# PhaseALeg.net
KiCad netlist of a schematic drawn in Altium Designer
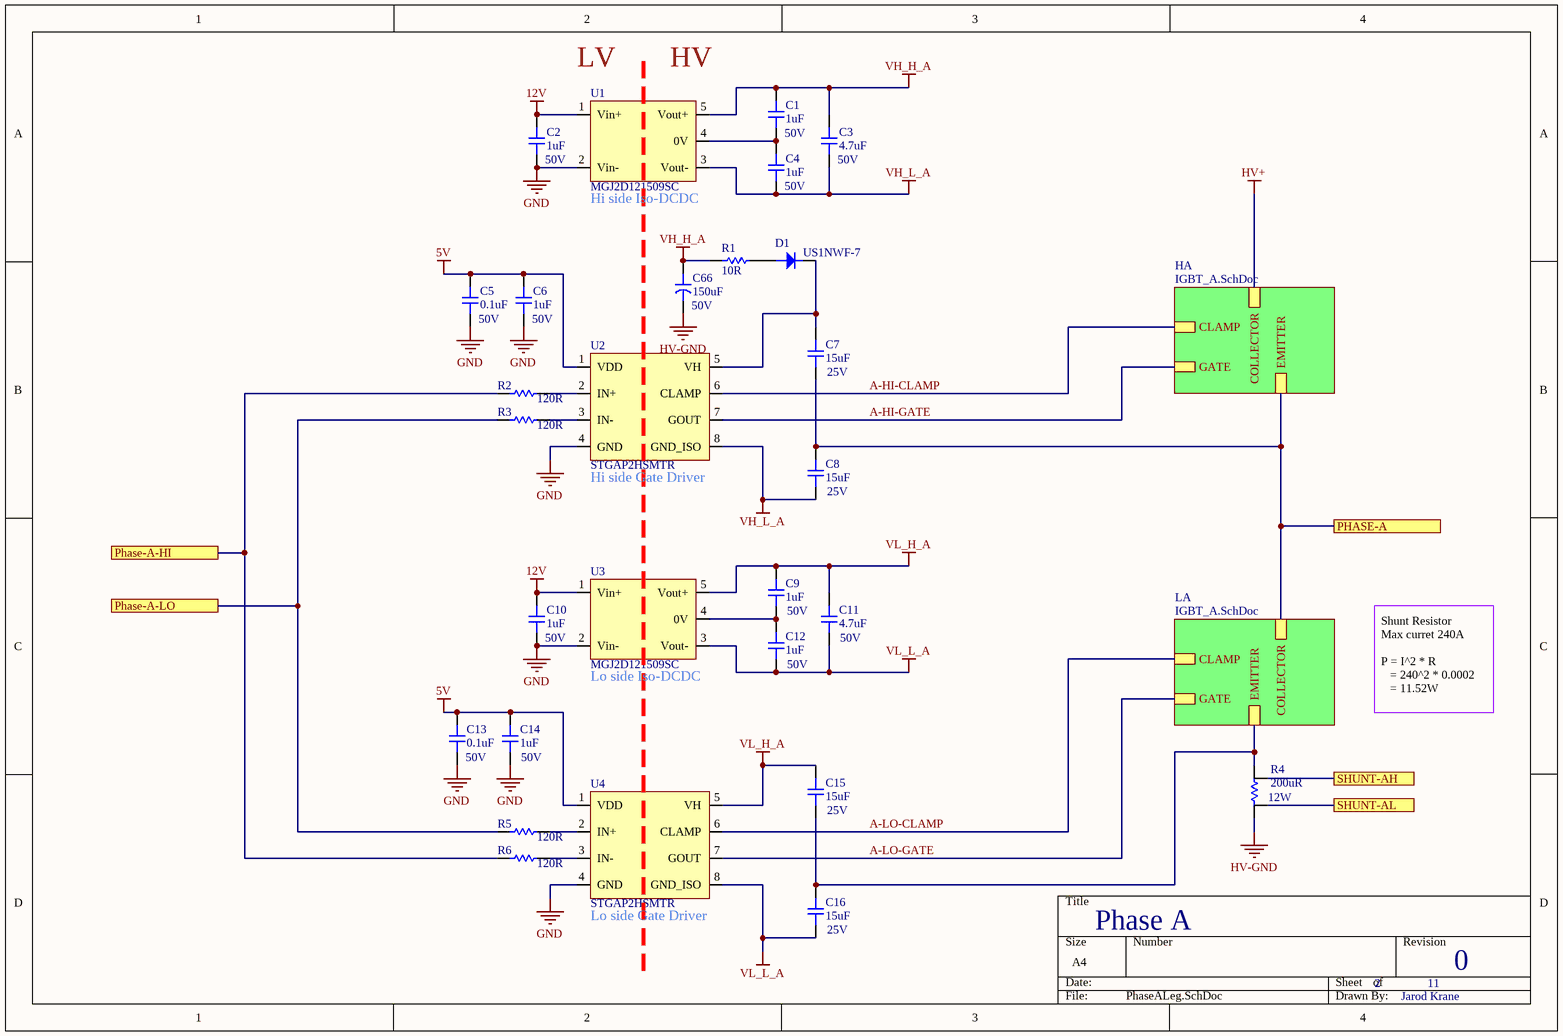
[diagram p0: PhaseALeg.SchDoc]

(export (version "E")
  (design (tool "Eeschema 10.0.6"))
  (components
    (comp (ref "C1")
      (value "1uF")
      (footprint "CAP-0805")
      (description "CAP CER 1UF 50V X5R 0805")
      (fields
        (field (name "MANUFACTURER") "KEMET")
        (field (name "MANUFACTURER PART NUMBER") "C0805C105K5PACTU")
        (field (name "VOLTAGE RATING") "50V")
      )
      (libsource (lib "InverterSCHLib") (part "0805-1uF-50V"))
    )
    (comp (ref "C2")
      (value "1uF")
      (footprint "CAP-0805")
      (description "CAP CER 1UF 50V X5R 0805")
      (fields
        (field (name "MANUFACTURER") "KEMET")
        (field (name "MANUFACTURER PART NUMBER") "C0805C105K5PACTU")
        (field (name "VOLTAGE RATING") "50V")
      )
      (libsource (lib "InverterSCHLib") (part "0805-1uF-50V"))
    )
    (comp (ref "C3")
      (value "4.7uF")
      (footprint "CAP-1206")
      (description "CAP CER 4.7UF 50V X7R 1206")
      (fields
        (field (name "MANUFACTURER") "TDK")
        (field (name "MANUFACTURER PART NUMBER") "C3216X7R1H475K160AC")
        (field (name "VOLTAGE RATING") "50V")
      )
      (libsource (lib "InverterSCHLib") (part "1206-4.7uF-50V"))
    )
    (comp (ref "C4")
      (value "1uF")
      (footprint "CAP-0805")
      (description "CAP CER 1UF 50V X5R 0805")
      (fields
        (field (name "MANUFACTURER") "KEMET")
        (field (name "MANUFACTURER PART NUMBER") "C0805C105K5PACTU")
        (field (name "VOLTAGE RATING") "50V")
      )
      (libsource (lib "InverterSCHLib") (part "0805-1uF-50V"))
    )
    (comp (ref "C5")
      (value "0.1uF")
      (footprint "CAP-0805")
      (description "CAP CER 0.1UF 50V Y5V 0805")
      (fields
        (field (name "MANUFACTURER") "KEMET")
        (field (name "MANUFACTURER PART NUMBER") "C0805C104Z5VACTU")
        (field (name "VOLTAGE") "50V")
      )
      (libsource (lib "InverterSCHLib") (part "0805-0.1uF-50V"))
    )
    (comp (ref "C6")
      (value "1uF")
      (footprint "CAP-0805")
      (description "CAP CER 1UF 50V X5R 0805")
      (fields
        (field (name "MANUFACTURER") "KEMET")
        (field (name "MANUFACTURER PART NUMBER") "C0805C105K5PACTU")
        (field (name "VOLTAGE RATING") "50V")
      )
      (libsource (lib "InverterSCHLib") (part "0805-1uF-50V"))
    )
    (comp (ref "C7")
      (value "15uF")
      (footprint "CAP-1812")
      (description "CAP CER 15UF 25V X7R 1812")
      (fields
        (field (name "MANUFACTURER") "TDK")
        (field (name "MANUFACTURER PART NUMBER") "C4532X7R1E156M280KB")
        (field (name "VOLTAGE") "25V")
      )
      (libsource (lib "InverterSCHLib") (part "1812-15uF-25V"))
    )
    (comp (ref "C8")
      (value "15uF")
      (footprint "CAP-1812")
      (description "CAP CER 15UF 25V X7R 1812")
      (fields
        (field (name "MANUFACTURER") "TDK")
        (field (name "MANUFACTURER PART NUMBER") "C4532X7R1E156M280KB")
        (field (name "VOLTAGE") "25V")
      )
      (libsource (lib "InverterSCHLib") (part "1812-15uF-25V"))
    )
    (comp (ref "C9")
      (value "1uF")
      (footprint "CAP-0805")
      (description "CAP CER 1UF 50V X5R 0805")
      (fields
        (field (name "MANUFACTURER") "KEMET")
        (field (name "MANUFACTURER PART NUMBER") "C0805C105K5PACTU")
        (field (name "VOLTAGE RATING") "50V")
      )
      (libsource (lib "InverterSCHLib") (part "0805-1uF-50V"))
    )
    (comp (ref "C10")
      (value "1uF")
      (footprint "CAP-0805")
      (description "CAP CER 1UF 50V X5R 0805")
      (fields
        (field (name "MANUFACTURER") "KEMET")
        (field (name "MANUFACTURER PART NUMBER") "C0805C105K5PACTU")
        (field (name "VOLTAGE RATING") "50V")
      )
      (libsource (lib "InverterSCHLib") (part "0805-1uF-50V"))
    )
    (comp (ref "C11")
      (value "4.7uF")
      (footprint "CAP-1206")
      (description "CAP CER 4.7UF 50V X7R 1206")
      (fields
        (field (name "MANUFACTURER") "TDK")
        (field (name "MANUFACTURER PART NUMBER") "C3216X7R1H475K160AC")
        (field (name "VOLTAGE RATING") "50V")
      )
      (libsource (lib "InverterSCHLib") (part "1206-4.7uF-50V"))
    )
    (comp (ref "C12")
      (value "1uF")
      (footprint "CAP-0805")
      (description "CAP CER 1UF 50V X5R 0805")
      (fields
        (field (name "MANUFACTURER") "KEMET")
        (field (name "MANUFACTURER PART NUMBER") "C0805C105K5PACTU")
        (field (name "VOLTAGE RATING") "50V")
      )
      (libsource (lib "InverterSCHLib") (part "0805-1uF-50V"))
    )
    (comp (ref "C13")
      (value "0.1uF")
      (footprint "CAP-0805")
      (description "CAP CER 0.1UF 50V Y5V 0805")
      (fields
        (field (name "MANUFACTURER") "KEMET")
        (field (name "MANUFACTURER PART NUMBER") "C0805C104Z5VACTU")
        (field (name "VOLTAGE") "50V")
      )
      (libsource (lib "InverterSCHLib") (part "0805-0.1uF-50V"))
    )
    (comp (ref "C14")
      (value "1uF")
      (footprint "CAP-0805")
      (description "CAP CER 1UF 50V X5R 0805")
      (fields
        (field (name "MANUFACTURER") "KEMET")
        (field (name "MANUFACTURER PART NUMBER") "C0805C105K5PACTU")
        (field (name "VOLTAGE RATING") "50V")
      )
      (libsource (lib "InverterSCHLib") (part "0805-1uF-50V"))
    )
    (comp (ref "C15")
      (value "15uF")
      (footprint "CAP-1812")
      (description "CAP CER 15UF 25V X7R 1812")
      (fields
        (field (name "MANUFACTURER") "TDK")
        (field (name "MANUFACTURER PART NUMBER") "C4532X7R1E156M280KB")
        (field (name "VOLTAGE") "25V")
      )
      (libsource (lib "InverterSCHLib") (part "1812-15uF-25V"))
    )
    (comp (ref "C16")
      (value "15uF")
      (footprint "CAP-1812")
      (description "CAP CER 15UF 25V X7R 1812")
      (fields
        (field (name "MANUFACTURER") "TDK")
        (field (name "MANUFACTURER PART NUMBER") "C4532X7R1E156M280KB")
        (field (name "VOLTAGE") "25V")
      )
      (libsource (lib "InverterSCHLib") (part "1812-15uF-25V"))
    )
    (comp (ref "C66")
      (value "150uF")
      (footprint "CAPCAN-10mm")
      (description "CAP POLYMER HYBRID 150UF 50V SMD")
      (fields
        (field (name "MANUFACTURER") "Panasonic")
        (field (name "MANUFACTURER PART NUMBER") "EEHZS1H151P")
        (field (name "VOLTAGE") "50V")
      )
      (libsource (lib "InverterSCHLib") (part "10mm-150uF-50V"))
    )
    (comp (ref "D1")
      (value "US1NWF-7")
      (footprint "DIOM2718X12N")
      (description "DIODE GEN PURP 1.2KV 1A SOD123F")
      (fields (field (name "MANUFACTURER") "Diodes"))
      (libsource (lib "InverterSCHLib") (part "Diode 1.2KV-1A"))
    )
    (comp (ref "R1")
      (value "10R")
      (footprint "RES-0603")
      (description "RES SMD 10 OHM 1% 1/10W 0603")
      (fields
        (field (name "MANUFACTURER") "Yageo")
        (field (name "MANUFACTURER PART NUMBER") "RC0603FR-0710RL")
      )
      (libsource (lib "InverterSCHLib") (part "0603-10R"))
    )
    (comp (ref "R2")
      (value "120R")
      (footprint "RES-0603")
      (description "RES SMD 120 OHM 1% 1/10W 0603")
      (fields
        (field (name "MANUFACTURER") "Yageo")
        (field (name "MANUFACTURER PART NUMBER") "RC0603FR-07120RL")
      )
      (libsource (lib "InverterSCHLib") (part "0603-120R"))
    )
    (comp (ref "R3")
      (value "120R")
      (footprint "RES-0603")
      (description "RES SMD 120 OHM 1% 1/10W 0603")
      (fields
        (field (name "MANUFACTURER") "Yageo")
        (field (name "MANUFACTURER PART NUMBER") "RC0603FR-07120RL")
      )
      (libsource (lib "InverterSCHLib") (part "0603-120R"))
    )
    (comp (ref "R4")
      (value "200uR")
      (footprint "RES-SHUNT")
      (description "RES SMD 200 UOHM 1% 12W 3920")
      (fields
        (field (name "MANUFACTURER") "Bourns")
        (field (name "MANUFACTURER PART NUMBER") "CSS2H-3920R-L200FE")
        (field (name "POWER") "12W")
      )
      (libsource (lib "InverterSCHLib") (part "3920-200uR-SHUNT"))
    )
    (comp (ref "R5")
      (value "120R")
      (footprint "RES-0603")
      (description "RES SMD 120 OHM 1% 1/10W 0603")
      (fields
        (field (name "MANUFACTURER") "Yageo")
        (field (name "MANUFACTURER PART NUMBER") "RC0603FR-07120RL")
      )
      (libsource (lib "InverterSCHLib") (part "0603-120R"))
    )
    (comp (ref "R6")
      (value "120R")
      (footprint "RES-0603")
      (description "RES SMD 120 OHM 1% 1/10W 0603")
      (fields
        (field (name "MANUFACTURER") "Yageo")
        (field (name "MANUFACTURER PART NUMBER") "RC0603FR-07120RL")
      )
      (libsource (lib "InverterSCHLib") (part "0603-120R"))
    )
    (comp (ref "U1")
      (value "MGJ2D121509SC")
      (footprint "MGJ2")
      (description "Isolated Module DC DC Converter Output 15V -8.7V - 80mA, 40mA 10.8V - 13.2V Input")
      (fields (field (name "MANUFACTURER") "Murata"))
      (libsource (lib "InverterSCHLib") (part "15V/-8.7V"))
    )
    (comp (ref "U2")
      (value "STGAP2HSMTR")
      (footprint "SO-8W")
      (description "GALVANICALLY ISOLATED 4 A SINGLE GATE DRIVER")
      (fields
        (field (name "MANUFACTURER") "Samtec")
        (field (name "MANUFACTURER PART NUMBER") "ERF8-010-07.0-L-DV-L-K-TR")
      )
      (libsource (lib "InverterSCHLib") (part "STGAP2HSMTR"))
    )
    (comp (ref "U3")
      (value "MGJ2D121509SC")
      (footprint "MGJ2")
      (description "Isolated Module DC DC Converter Output 15V -8.7V - 80mA, 40mA 10.8V - 13.2V Input")
      (fields (field (name "MANUFACTURER") "Murata"))
      (libsource (lib "InverterSCHLib") (part "15V/-8.7V"))
    )
    (comp (ref "U4")
      (value "STGAP2HSMTR")
      (footprint "SO-8W")
      (description "GALVANICALLY ISOLATED 4 A SINGLE GATE DRIVER")
      (fields
        (field (name "MANUFACTURER") "Samtec")
        (field (name "MANUFACTURER PART NUMBER") "ERF8-010-07.0-L-DV-L-K-TR")
      )
      (libsource (lib "InverterSCHLib") (part "STGAP2HSMTR"))
    )
  )
  (nets
    (net (code "1") (name "/A-HI-CLAMP") (class "Default")
      (node (ref "U2") (pin "6") (pinfunction "CLAMP_6") (pintype "passive"))
    )
    (net (code "2") (name "/A-HI-GATE") (class "Default")
      (node (ref "U2") (pin "7") (pinfunction "GOUT_7") (pintype "passive"))
    )
    (net (code "3") (name "/A-LO-CLAMP") (class "Default")
      (node (ref "U4") (pin "6") (pinfunction "CLAMP_6") (pintype "passive"))
    )
    (net (code "4") (name "/A-LO-GATE") (class "Default")
      (node (ref "U4") (pin "7") (pinfunction "GOUT_7") (pintype "passive"))
    )
    (net (code "5") (name "/EMITTER") (class "Default")
      (node (ref "C15") (pin "1") (pinfunction "1_1") (pintype "passive"))
      (node (ref "C16") (pin "2") (pinfunction "2_2") (pintype "passive"))
      (node (ref "R4") (pin "2") (pinfunction "2_2") (pintype "passive"))
    )
    (net (code "6") (name "/PHASE-A") (class "Default")
      (node (ref "C7") (pin "1") (pinfunction "1_1") (pintype "passive"))
      (node (ref "C8") (pin "2") (pinfunction "2_2") (pintype "passive"))
    )
    (net (code "7") (name "/Phase-A-HI") (class "Default")
      (node (ref "R2") (pin "1") (pinfunction "1_1") (pintype "passive"))
      (node (ref "R6") (pin "1") (pinfunction "1_1") (pintype "passive"))
    )
    (net (code "8") (name "/Phase-A-LO") (class "Default")
      (node (ref "R3") (pin "1") (pinfunction "1_1") (pintype "passive"))
      (node (ref "R5") (pin "1") (pinfunction "1_1") (pintype "passive"))
    )
    (net (code "9") (name "/SHUNT-AH") (class "Default")
      (node (ref "R4") (pin "4") (pinfunction "4_4") (pintype "passive"))
    )
    (net (code "10") (name "/SHUNT-AL") (class "Default")
      (node (ref "R4") (pin "3") (pinfunction "3_3") (pintype "passive"))
    )
    (net (code "11") (name "5V") (class "Default")
      (node (ref "C13") (pin "2") (pinfunction "2_2") (pintype "passive"))
      (node (ref "C14") (pin "2") (pinfunction "2_2") (pintype "passive"))
      (node (ref "C5") (pin "2") (pinfunction "2_2") (pintype "passive"))
      (node (ref "C6") (pin "2") (pinfunction "2_2") (pintype "passive"))
      (node (ref "U2") (pin "1") (pinfunction "VDD_1") (pintype "passive"))
      (node (ref "U4") (pin "1") (pinfunction "VDD_1") (pintype "passive"))
    )
    (net (code "12") (name "12V") (class "Default")
      (node (ref "C10") (pin "2") (pinfunction "2_2") (pintype "passive"))
      (node (ref "C2") (pin "2") (pinfunction "2_2") (pintype "passive"))
      (node (ref "U1") (pin "1") (pinfunction "Vin+_1") (pintype "passive"))
      (node (ref "U3") (pin "1") (pinfunction "Vin+_1") (pintype "passive"))
    )
    (net (code "13") (name "GND") (class "Default")
      (node (ref "C10") (pin "1") (pinfunction "1_1") (pintype "passive"))
      (node (ref "C13") (pin "1") (pinfunction "1_1") (pintype "passive"))
      (node (ref "C14") (pin "1") (pinfunction "1_1") (pintype "passive"))
      (node (ref "C2") (pin "1") (pinfunction "1_1") (pintype "passive"))
      (node (ref "C5") (pin "1") (pinfunction "1_1") (pintype "passive"))
      (node (ref "C6") (pin "1") (pinfunction "1_1") (pintype "passive"))
      (node (ref "U1") (pin "2") (pinfunction "Vin-_2") (pintype "passive"))
      (node (ref "U2") (pin "4") (pinfunction "GND_4") (pintype "passive"))
      (node (ref "U3") (pin "2") (pinfunction "Vin-_2") (pintype "passive"))
      (node (ref "U4") (pin "4") (pinfunction "GND_4") (pintype "passive"))
    )
    (net (code "15") (name "HV-GND") (class "Default")
      (node (ref "C66") (pin "2") (pinfunction "2_2") (pintype "passive"))
      (node (ref "R4") (pin "1") (pinfunction "1_1") (pintype "passive"))
    )
    (net (code "16") (name "Net-(D1-Pad2)") (class "Default")
      (node (ref "D1") (pin "2") (pinfunction "2_2") (pintype "passive"))
      (node (ref "R1") (pin "2") (pinfunction "2_2") (pintype "passive"))
    )
    (net (code "17") (name "Net-(U1-0V)") (class "Default")
      (node (ref "C1") (pin "1") (pinfunction "1_1") (pintype "passive"))
      (node (ref "C4") (pin "2") (pinfunction "2_2") (pintype "passive"))
      (node (ref "U1") (pin "4") (pinfunction "0V_4") (pintype "passive"))
    )
    (net (code "18") (name "Net-(U2-IN+)") (class "Default")
      (node (ref "R2") (pin "2") (pinfunction "2_2") (pintype "passive"))
      (node (ref "U2") (pin "2") (pinfunction "IN+_2") (pintype "passive"))
    )
    (net (code "19") (name "Net-(U2-IN-)") (class "Default")
      (node (ref "R3") (pin "2") (pinfunction "2_2") (pintype "passive"))
      (node (ref "U2") (pin "3") (pinfunction "IN-_3") (pintype "passive"))
    )
    (net (code "20") (name "Net-(U2-VH)") (class "Default")
      (node (ref "C7") (pin "2") (pinfunction "2_2") (pintype "passive"))
      (node (ref "D1") (pin "1") (pinfunction "1_1") (pintype "passive"))
      (node (ref "U2") (pin "5") (pinfunction "VH_5") (pintype "passive"))
    )
    (net (code "21") (name "Net-(U3-0V)") (class "Default")
      (node (ref "C12") (pin "2") (pinfunction "2_2") (pintype "passive"))
      (node (ref "C9") (pin "1") (pinfunction "1_1") (pintype "passive"))
      (node (ref "U3") (pin "4") (pinfunction "0V_4") (pintype "passive"))
    )
    (net (code "22") (name "Net-(U4-IN+)") (class "Default")
      (node (ref "R5") (pin "2") (pinfunction "2_2") (pintype "passive"))
      (node (ref "U4") (pin "2") (pinfunction "IN+_2") (pintype "passive"))
    )
    (net (code "23") (name "Net-(U4-IN-)") (class "Default")
      (node (ref "R6") (pin "2") (pinfunction "2_2") (pintype "passive"))
      (node (ref "U4") (pin "3") (pinfunction "IN-_3") (pintype "passive"))
    )
    (net (code "24") (name "VH_H_A") (class "Default")
      (node (ref "C1") (pin "2") (pinfunction "2_2") (pintype "passive"))
      (node (ref "C3") (pin "2") (pinfunction "2_2") (pintype "passive"))
      (node (ref "C66") (pin "1") (pinfunction "1_1") (pintype "passive"))
      (node (ref "R1") (pin "1") (pinfunction "1_1") (pintype "passive"))
      (node (ref "U1") (pin "5") (pinfunction "Vout+_5") (pintype "passive"))
    )
    (net (code "25") (name "VH_L_A") (class "Default")
      (node (ref "C3") (pin "1") (pinfunction "1_1") (pintype "passive"))
      (node (ref "C4") (pin "1") (pinfunction "1_1") (pintype "passive"))
      (node (ref "C8") (pin "1") (pinfunction "1_1") (pintype "passive"))
      (node (ref "U1") (pin "3") (pinfunction "Vout-_3") (pintype "passive"))
      (node (ref "U2") (pin "8") (pinfunction "GND_ISO_8") (pintype "passive"))
    )
    (net (code "26") (name "VL_H_A") (class "Default")
      (node (ref "C11") (pin "2") (pinfunction "2_2") (pintype "passive"))
      (node (ref "C15") (pin "2") (pinfunction "2_2") (pintype "passive"))
      (node (ref "C9") (pin "2") (pinfunction "2_2") (pintype "passive"))
      (node (ref "U3") (pin "5") (pinfunction "Vout+_5") (pintype "passive"))
      (node (ref "U4") (pin "5") (pinfunction "VH_5") (pintype "passive"))
    )
    (net (code "27") (name "VL_L_A") (class "Default")
      (node (ref "C11") (pin "1") (pinfunction "1_1") (pintype "passive"))
      (node (ref "C12") (pin "1") (pinfunction "1_1") (pintype "passive"))
      (node (ref "C16") (pin "1") (pinfunction "1_1") (pintype "passive"))
      (node (ref "U3") (pin "3") (pinfunction "Vout-_3") (pintype "passive"))
      (node (ref "U4") (pin "8") (pinfunction "GND_ISO_8") (pintype "passive"))
    )
  )
)
